# nrf905.net
KiCad netlist of a schematic drawn in Altium Designer
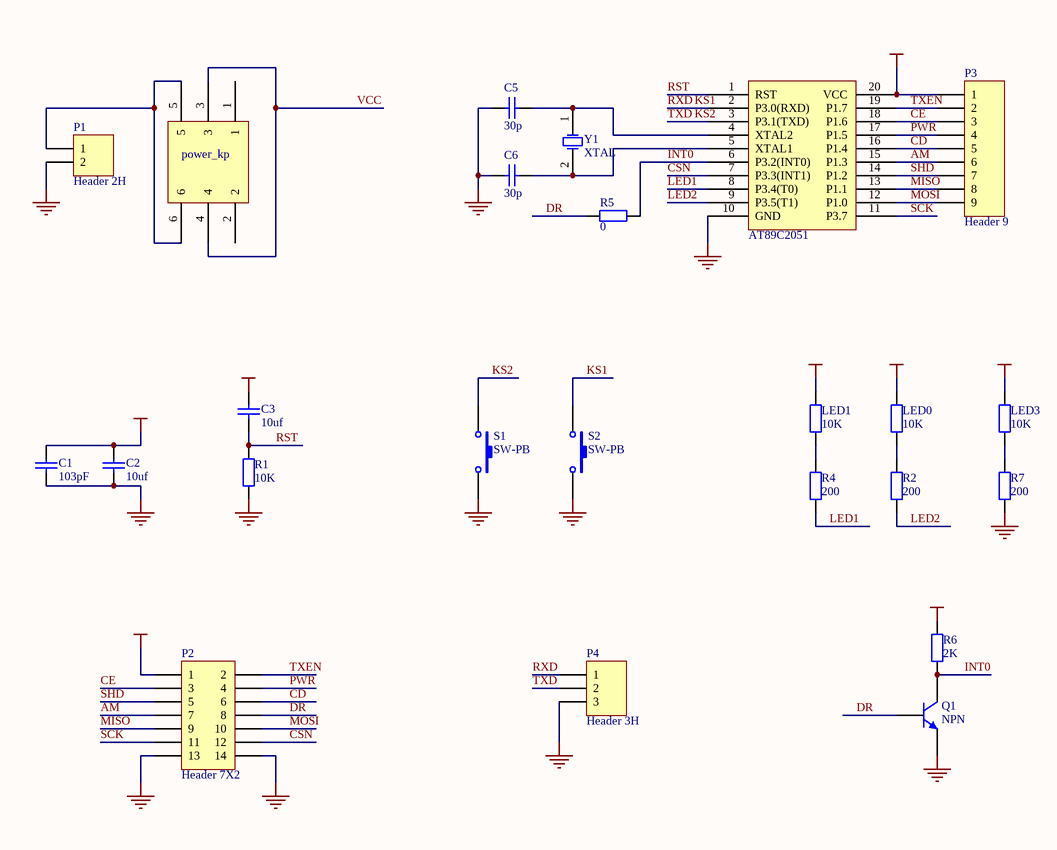
[diagram p0: nrf905.SchDoc]

(export (version "E")
  (design (tool "Eeschema 10.0.6"))
  (components
    (comp (ref "AT89C2051")
      (value "51")
      (footprint "CDIP20")
      (libsource (lib "MY SCHLIB") (part "at89c2051"))
    )
    (comp (ref "C1")
      (value "103pF")
      (footprint "C1608-0603")
      (description "Capacitor")
      (fields (field (name "Comment") "Cap") (field (name "PUBLISHER") "Altium Limited"))
      (libsource (lib "Miscellaneous Devices") (part "Cap"))
    )
    (comp (ref "C2")
      (value "10uf")
      (footprint "CC3216-1206")
      (description "Capacitor")
      (fields (field (name "Comment") "Cap") (field (name "PUBLISHER") "Altium Limited"))
      (libsource (lib "Miscellaneous Devices") (part "Cap"))
    )
    (comp (ref "C3")
      (value "10uf")
      (footprint "R2012-0805")
      (description "Capacitor")
      (fields (field (name "Comment") "Cap") (field (name "PUBLISHER") "Altium Limited"))
      (libsource (lib "Miscellaneous Devices") (part "Cap"))
    )
    (comp (ref "C5")
      (value "30p")
      (footprint "C1608-0603")
      (description "Capacitor")
      (fields (field (name "Comment") "Cap") (field (name "PUBLISHER") "Altium Limited"))
      (libsource (lib "Miscellaneous Devices") (part "Cap"))
    )
    (comp (ref "C6")
      (value "30p")
      (footprint "C1608-0603")
      (description "Capacitor")
      (fields (field (name "Comment") "Cap") (field (name "PUBLISHER") "Altium Limited"))
      (libsource (lib "Miscellaneous Devices") (part "Cap"))
    )
    (comp (ref "LED0")
      (value "10K")
      (footprint "LED_3")
      (description "Resistor")
      (fields (field (name "Comment") "Res2") (field (name "PUBLISHER") "Altium Limited"))
      (libsource (lib "") (part "Res2_1"))
    )
    (comp (ref "LED1")
      (value "10K")
      (footprint "LED_3")
      (description "Resistor")
      (fields (field (name "Comment") "Res2") (field (name "PUBLISHER") "Altium Limited"))
      (libsource (lib "") (part "Res2_1"))
    )
    (comp (ref "LED3")
      (value "10K")
      (footprint "LED_3")
      (description "Resistor")
      (fields (field (name "Comment") "Res2") (field (name "PUBLISHER") "Altium Limited"))
      (libsource (lib "") (part "Res2_1"))
    )
    (comp (ref "P1")
      (value "Header 2H")
      (footprint "HDR1X2H")
      (description "Header, 2-Pin, Right Angle")
      (fields (field (name "PUBLISHER") "Altium Limited"))
      (libsource (lib "Miscellaneous Connectors") (part "Header 2H"))
    )
    (comp (ref "P2")
      (value "Header 7X2")
      (footprint "HDR2X7")
      (description "Header, 7-Pin, Dual row")
      (fields (field (name "PUBLISHER") "Altium Limited"))
      (libsource (lib "Miscellaneous Connectors") (part "Header 7X2"))
    )
    (comp (ref "P3")
      (value "Header 9")
      (footprint "HDR1X9")
      (description "Header, 9-Pin")
      (fields (field (name "PUBLISHER") "Altium Limited"))
      (libsource (lib "Miscellaneous Connectors") (part "Header 9"))
    )
    (comp (ref "P4")
      (value "Header 3H")
      (footprint "HDR1X3H")
      (description "Header, 3-Pin, Right Angle")
      (fields (field (name "PUBLISHER") "Altium Limited"))
      (libsource (lib "Miscellaneous Connectors") (part "Header 3H"))
    )
    (comp (ref "power_kp") (value "key3") (footprint "S_2") (libsource (lib "KEY") (part "key3")))
    (comp (ref "Q1")
      (value "NPN")
      (footprint "SOT23")
      (description "NPN Bipolar Transistor")
      (fields (field (name "PUBLISHER") "Altium Limited"))
      (libsource (lib "Miscellaneous Devices") (part "NPN"))
    )
    (comp (ref "R1")
      (value "10K")
      (footprint "C1608-0603")
      (description "Resistor")
      (fields (field (name "Comment") "Res2") (field (name "PUBLISHER") "Altium Limited"))
      (libsource (lib "") (part "Res2_1"))
    )
    (comp (ref "R2")
      (value "200")
      (footprint "C1608-0603")
      (description "Resistor")
      (fields (field (name "Comment") "Res2") (field (name "PUBLISHER") "Altium Limited"))
      (libsource (lib "") (part "Res2_1"))
    )
    (comp (ref "R4")
      (value "200")
      (footprint "C1608-0603")
      (description "Resistor")
      (fields (field (name "Comment") "Res2") (field (name "PUBLISHER") "Altium Limited"))
      (libsource (lib "") (part "Res2_1"))
    )
    (comp (ref "R5")
      (value "0")
      (footprint "C1608-0603")
      (description "Resistor")
      (fields (field (name "Comment") "Res2") (field (name "PUBLISHER") "Altium Limited"))
      (libsource (lib "") (part "Res2_2"))
    )
    (comp (ref "R6")
      (value "2K")
      (footprint "C1608-0603")
      (description "Resistor")
      (fields (field (name "Comment") "Res2") (field (name "PUBLISHER") "Altium Limited"))
      (libsource (lib "Miscellaneous Devices") (part "Res2"))
    )
    (comp (ref "R7")
      (value "200")
      (footprint "C1608-0603")
      (description "Resistor")
      (fields (field (name "Comment") "Res2") (field (name "PUBLISHER") "Altium Limited"))
      (libsource (lib "") (part "Res2_1"))
    )
    (comp (ref "S1")
      (value "SW-PB")
      (footprint "PCBComponent_1")
      (description "Switch")
      (fields (field (name "PUBLISHER") "Altium Limited"))
      (libsource (lib "Miscellaneous Devices") (part "SW-PB"))
    )
    (comp (ref "S2")
      (value "SW-PB")
      (footprint "PCBComponent_1")
      (description "Switch")
      (fields (field (name "PUBLISHER") "Altium Limited"))
      (libsource (lib "Miscellaneous Devices") (part "SW-PB"))
    )
    (comp (ref "Y1")
      (value "XTAL")
      (footprint "CRYSTAL")
      (description "Crystal Oscillator")
      (fields (field (name "PUBLISHER") "Altium Limited"))
      (libsource (lib "Miscellaneous Devices") (part "XTAL"))
    )
  )
  (nets
    (net (code "1") (name "/AM") (class "Default")
      (node (ref "AT89C2051") (pin "15") (pinfunction "P1.3_15") (pintype "passive"))
      (node (ref "P2") (pin "7") (pinfunction "7_7") (pintype "passive"))
      (node (ref "P3") (pin "6") (pinfunction "6_6") (pintype "passive"))
    )
    (net (code "2") (name "/CD") (class "Default")
      (node (ref "AT89C2051") (pin "16") (pinfunction "P1.4_16") (pintype "passive"))
      (node (ref "P2") (pin "6") (pinfunction "6_6") (pintype "passive"))
      (node (ref "P3") (pin "5") (pinfunction "5_5") (pintype "passive"))
    )
    (net (code "3") (name "/CE") (class "Default")
      (node (ref "AT89C2051") (pin "18") (pinfunction "P1.6_18") (pintype "passive"))
      (node (ref "P2") (pin "3") (pinfunction "3_3") (pintype "passive"))
      (node (ref "P3") (pin "3") (pinfunction "3_3") (pintype "passive"))
    )
    (net (code "4") (name "/CSN") (class "Default")
      (node (ref "AT89C2051") (pin "7") (pinfunction "P3.3(INT1)_7") (pintype "passive"))
      (node (ref "P2") (pin "12") (pinfunction "12_12") (pintype "passive"))
    )
    (net (code "5") (name "/DR") (class "Default")
      (node (ref "P2") (pin "8") (pinfunction "8_8") (pintype "passive"))
      (node (ref "Q1") (pin "1") (pinfunction "B_1") (pintype "passive"))
      (node (ref "R5") (pin "2") (pinfunction "2_2") (pintype "passive"))
    )
    (net (code "6") (name "/INT0") (class "Default")
      (node (ref "AT89C2051") (pin "6") (pinfunction "P3.2(INT0)_6") (pintype "passive"))
      (node (ref "Q1") (pin "3") (pinfunction "C_3") (pintype "passive"))
      (node (ref "R5") (pin "1") (pinfunction "1_1") (pintype "passive"))
      (node (ref "R6") (pin "2") (pinfunction "2_2") (pintype "passive"))
    )
    (net (code "7") (name "/KS1") (class "Default")
      (node (ref "AT89C2051") (pin "2") (pinfunction "P3.0(RXD)_2") (pintype "passive"))
      (node (ref "P4") (pin "1") (pinfunction "1_1") (pintype "passive"))
      (node (ref "S2") (pin "1") (pinfunction "1_1") (pintype "passive"))
    )
    (net (code "8") (name "/KS2") (class "Default")
      (node (ref "AT89C2051") (pin "3") (pinfunction "P3.1(TXD)_3") (pintype "passive"))
      (node (ref "P4") (pin "2") (pinfunction "2_2") (pintype "passive"))
      (node (ref "S1") (pin "1") (pinfunction "1_1") (pintype "passive"))
    )
    (net (code "9") (name "/LED1") (class "Default")
      (node (ref "AT89C2051") (pin "8") (pinfunction "P3.4(T0)_8") (pintype "passive"))
      (node (ref "R4") (pin "1") (pinfunction "1_1") (pintype "passive"))
    )
    (net (code "10") (name "/LED2") (class "Default")
      (node (ref "AT89C2051") (pin "9") (pinfunction "P3.5(T1)_9") (pintype "passive"))
      (node (ref "R2") (pin "1") (pinfunction "1_1") (pintype "passive"))
    )
    (net (code "11") (name "/MISO") (class "Default")
      (node (ref "AT89C2051") (pin "13") (pinfunction "P1.1_13") (pintype "passive"))
      (node (ref "P2") (pin "9") (pinfunction "9_9") (pintype "passive"))
      (node (ref "P3") (pin "8") (pinfunction "8_8") (pintype "passive"))
    )
    (net (code "12") (name "/MOSI") (class "Default")
      (node (ref "AT89C2051") (pin "12") (pinfunction "P1.0_12") (pintype "passive"))
      (node (ref "P2") (pin "10") (pinfunction "10_10") (pintype "passive"))
      (node (ref "P3") (pin "9") (pinfunction "9_9") (pintype "passive"))
    )
    (net (code "13") (name "/PWR") (class "Default")
      (node (ref "AT89C2051") (pin "17") (pinfunction "P1.5_17") (pintype "passive"))
      (node (ref "P2") (pin "4") (pinfunction "4_4") (pintype "passive"))
      (node (ref "P3") (pin "4") (pinfunction "4_4") (pintype "passive"))
    )
    (net (code "14") (name "/RST") (class "Default")
      (node (ref "AT89C2051") (pin "1") (pinfunction "RST_1") (pintype "passive"))
      (node (ref "C3") (pin "1") (pinfunction "1_1") (pintype "passive"))
      (node (ref "R1") (pin "2") (pinfunction "2_2") (pintype "passive"))
    )
    (net (code "15") (name "/SCK") (class "Default")
      (node (ref "AT89C2051") (pin "11") (pinfunction "P3.7_11") (pintype "passive"))
      (node (ref "P2") (pin "11") (pinfunction "11_11") (pintype "passive"))
    )
    (net (code "16") (name "/SHD") (class "Default")
      (node (ref "AT89C2051") (pin "14") (pinfunction "P1.2_14") (pintype "passive"))
      (node (ref "P2") (pin "5") (pinfunction "5_5") (pintype "passive"))
      (node (ref "P3") (pin "7") (pinfunction "7_7") (pintype "passive"))
    )
    (net (code "17") (name "/TXEN") (class "Default")
      (node (ref "AT89C2051") (pin "19") (pinfunction "P1.7_19") (pintype "passive"))
      (node (ref "P2") (pin "2") (pinfunction "2_2") (pintype "passive"))
      (node (ref "P3") (pin "2") (pinfunction "2_2") (pintype "passive"))
    )
    (net (code "18") (name "GND") (class "Default")
      (node (ref "AT89C2051") (pin "10") (pinfunction "GND_10") (pintype "passive"))
      (node (ref "C1") (pin "2") (pinfunction "2_2") (pintype "passive"))
      (node (ref "C2") (pin "1") (pinfunction "1_1") (pintype "passive"))
      (node (ref "C5") (pin "1") (pinfunction "1_1") (pintype "passive"))
      (node (ref "C6") (pin "1") (pinfunction "1_1") (pintype "passive"))
      (node (ref "P1") (pin "2") (pinfunction "2_2") (pintype "passive"))
      (node (ref "P2") (pin "13") (pinfunction "13_13") (pintype "passive"))
      (node (ref "P2") (pin "14") (pinfunction "14_14") (pintype "passive"))
      (node (ref "P4") (pin "3") (pinfunction "3_3") (pintype "passive"))
      (node (ref "Q1") (pin "2") (pinfunction "E_2") (pintype "passive"))
      (node (ref "R1") (pin "1") (pinfunction "1_1") (pintype "passive"))
      (node (ref "R7") (pin "1") (pinfunction "1_1") (pintype "passive"))
      (node (ref "S1") (pin "2") (pinfunction "2_2") (pintype "passive"))
      (node (ref "S2") (pin "2") (pinfunction "2_2") (pintype "passive"))
    )
    (net (code "19") (name "Net-(AT89C2051-XTAL1)") (class "Default")
      (node (ref "AT89C2051") (pin "5") (pinfunction "XTAL1_5") (pintype "passive"))
      (node (ref "C6") (pin "2") (pinfunction "2_2") (pintype "passive"))
      (node (ref "Y1") (pin "2") (pinfunction "OSC2_2") (pintype "passive"))
    )
    (net (code "20") (name "Net-(AT89C2051-XTAL2)") (class "Default")
      (node (ref "AT89C2051") (pin "4") (pinfunction "XTAL2_4") (pintype "passive"))
      (node (ref "C5") (pin "2") (pinfunction "2_2") (pintype "passive"))
      (node (ref "Y1") (pin "1") (pinfunction "OSC1_1") (pintype "passive"))
    )
    (net (code "21") (name "Net-(LED0-Pad1)") (class "Default")
      (node (ref "LED0") (pin "1") (pinfunction "1_1") (pintype "passive"))
      (node (ref "R2") (pin "2") (pinfunction "2_2") (pintype "passive"))
    )
    (net (code "22") (name "Net-(LED1-Pad1)") (class "Default")
      (node (ref "LED1") (pin "1") (pinfunction "1_1") (pintype "passive"))
      (node (ref "R4") (pin "2") (pinfunction "2_2") (pintype "passive"))
    )
    (net (code "23") (name "Net-(LED3-Pad1)") (class "Default")
      (node (ref "LED3") (pin "1") (pinfunction "1_1") (pintype "passive"))
      (node (ref "R7") (pin "2") (pinfunction "2_2") (pintype "passive"))
    )
    (net (code "24") (name "Net-(P1-Pad1)") (class "Default")
      (node (ref "P1") (pin "1") (pinfunction "1_1") (pintype "passive"))
      (node (ref "power_kp") (pin "5") (pinfunction "5_5") (pintype "passive"))
      (node (ref "power_kp") (pin "6") (pinfunction "6_6") (pintype "passive"))
    )
    (net (code "25") (name "VCC") (class "Default")
      (node (ref "AT89C2051") (pin "20") (pinfunction "VCC_20") (pintype "passive"))
      (node (ref "C1") (pin "1") (pinfunction "1_1") (pintype "passive"))
      (node (ref "C2") (pin "2") (pinfunction "2_2") (pintype "passive"))
      (node (ref "C3") (pin "2") (pinfunction "2_2") (pintype "passive"))
      (node (ref "LED0") (pin "2") (pinfunction "2_2") (pintype "passive"))
      (node (ref "LED1") (pin "2") (pinfunction "2_2") (pintype "passive"))
      (node (ref "LED3") (pin "2") (pinfunction "2_2") (pintype "passive"))
      (node (ref "P2") (pin "1") (pinfunction "1_1") (pintype "passive"))
      (node (ref "P3") (pin "1") (pinfunction "1_1") (pintype "passive"))
      (node (ref "R6") (pin "1") (pinfunction "1_1") (pintype "passive"))
      (node (ref "power_kp") (pin "3") (pinfunction "3_3") (pintype "passive"))
      (node (ref "power_kp") (pin "4") (pinfunction "4_4") (pintype "passive"))
    )
    (net (code "26") (name "unconnected-(power_kp-Pad1)") (class "Default")
      (node (ref "power_kp") (pin "1") (pinfunction "1_1") (pintype "passive"))
    )
    (net (code "27") (name "unconnected-(power_kp-Pad2)") (class "Default")
      (node (ref "power_kp") (pin "2") (pinfunction "2_2") (pintype "passive"))
    )
  )
)
